# ZDR5V.net
KiCad netlist of a schematic drawn in EAGLE
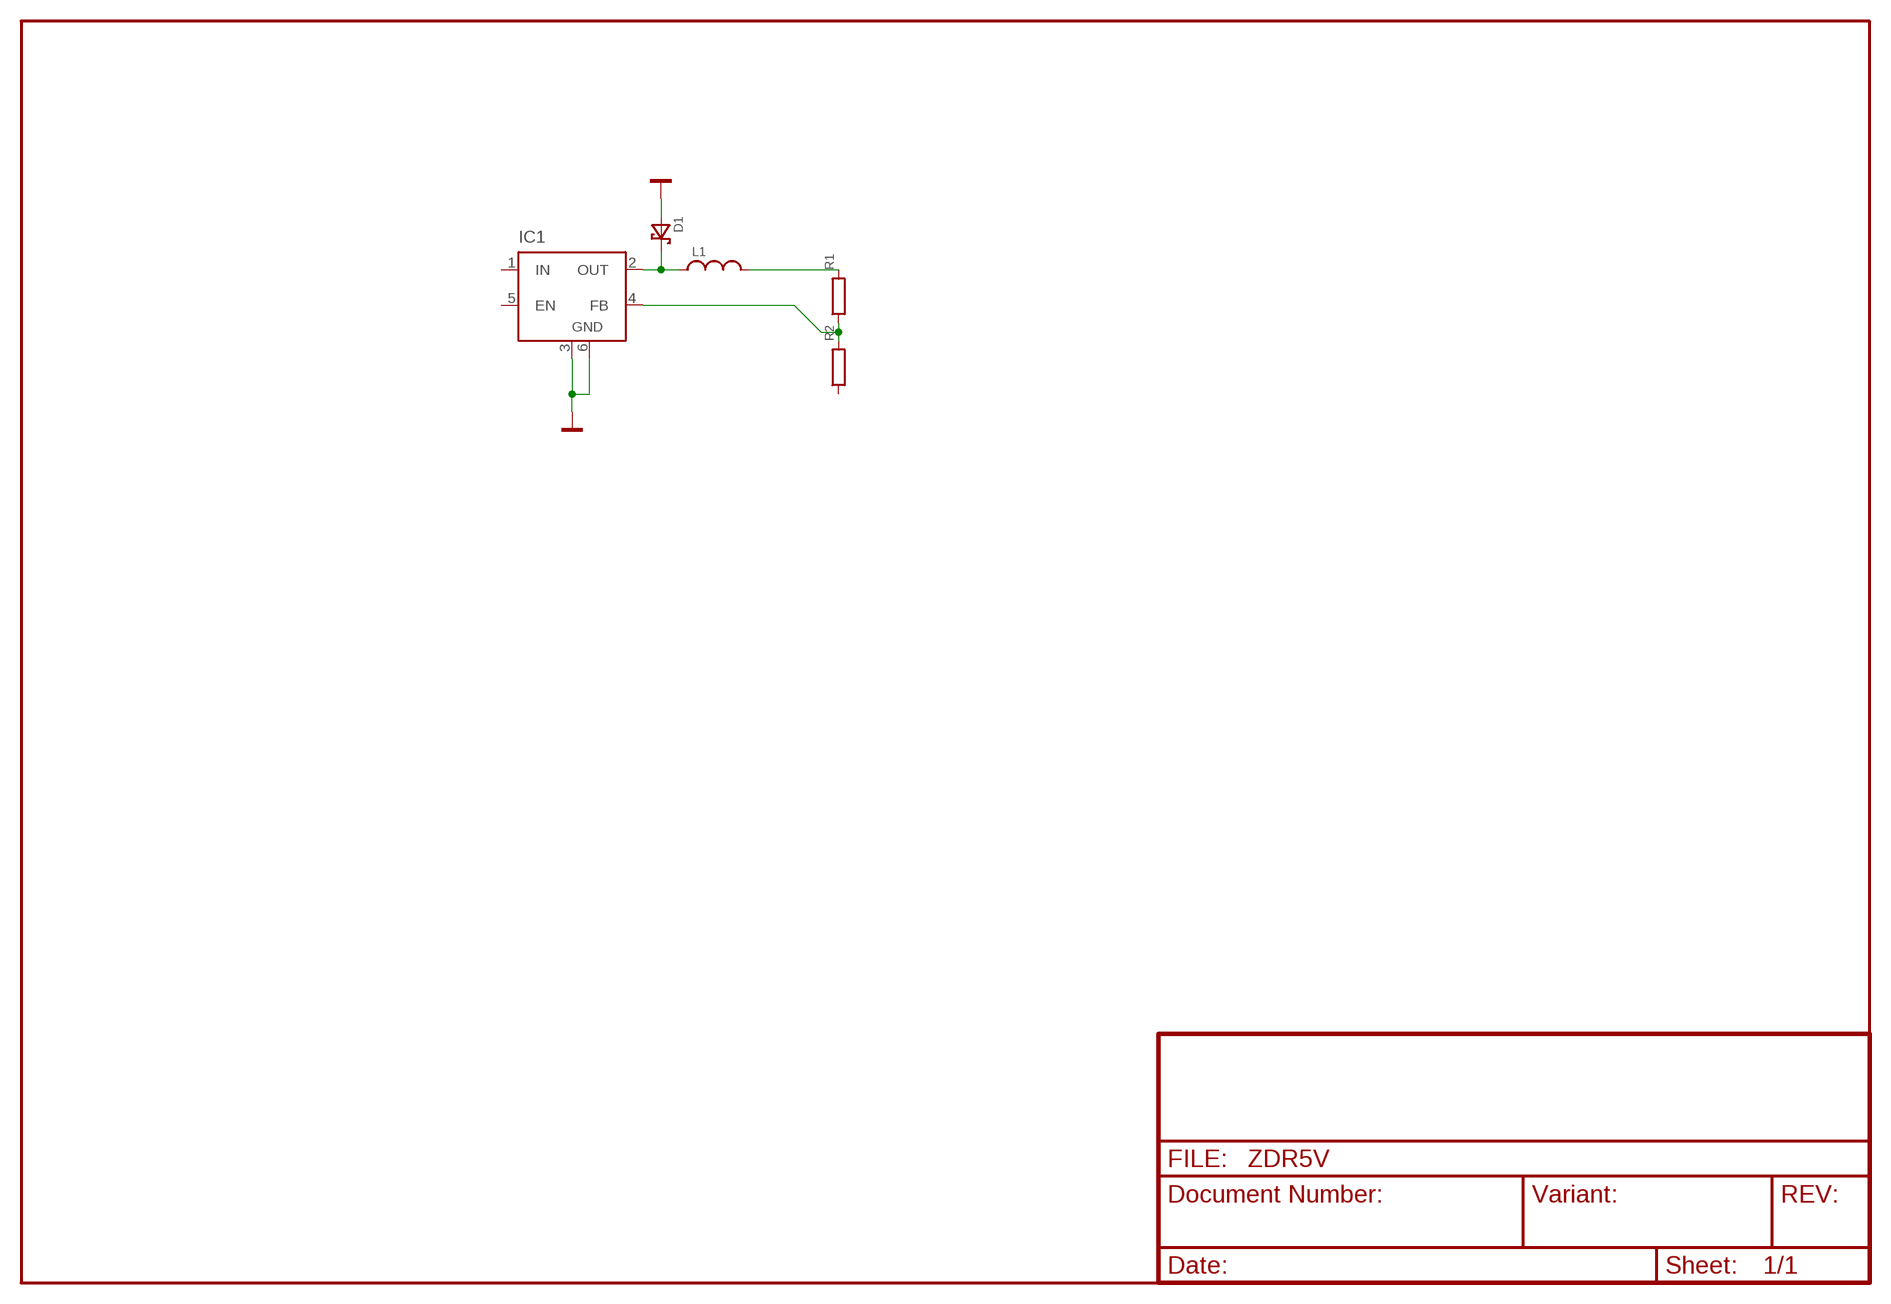
[diagram p0: schematic, sheet 1]

(export (version "E")
  (design (tool "Eeschema 10.0.6"))
  (components
    (comp (ref "D1")
      (value "D_SCHOTKY_SMB")
      (footprint "eagle-import:D_SMB")
      (libsource (lib "eagle-import") (part "D_SCHOTKY_SMB"))
    )
    (comp (ref "IC1")
      (value "LM2596S")
      (footprint "eagle-import:TO263-5")
      (libsource (lib "eagle-import") (part "LM2596S"))
    )
    (comp (ref "L1")
      (value "L_DE1209")
      (footprint "eagle-import:DE1209")
      (libsource (lib "eagle-import") (part "L_DE1209"))
    )
    (comp (ref "R1")
      (value "R_R0805")
      (footprint "eagle-import:0805")
      (libsource (lib "eagle-import") (part "R_R0805"))
    )
    (comp (ref "R2")
      (value "R_R0805")
      (footprint "eagle-import:0805")
      (libsource (lib "eagle-import") (part "R_R0805"))
    )
  )
  (nets
    (net (code "1") (name "GND") (class "Default")
      (node (ref "D1") (pin "A") (pinfunction "A_A") (pintype "passive"))
      (node (ref "IC1") (pin "3") (pinfunction "GND_3") (pintype "power_in"))
      (node (ref "IC1") (pin "6") (pinfunction "GND_6") (pintype "power_in"))
    )
    (net (code "2") (name "Net-(IC1-FB)") (class "Default")
      (node (ref "IC1") (pin "4") (pinfunction "FB_4") (pintype "input"))
      (node (ref "R1") (pin "1") (pinfunction "1_1") (pintype "passive"))
      (node (ref "R2") (pin "2") (pinfunction "2_2") (pintype "passive"))
    )
    (net (code "3") (name "Net-(IC1-OUT)") (class "Default")
      (node (ref "D1") (pin "K") (pinfunction "K_K") (pintype "passive"))
      (node (ref "IC1") (pin "2") (pinfunction "OUT_2") (pintype "output"))
      (node (ref "L1") (pin "2") (pinfunction "2_2") (pintype "passive"))
    )
    (net (code "4") (name "Net-(L1-Pad1)") (class "Default")
      (node (ref "L1") (pin "1") (pinfunction "1_1") (pintype "passive"))
      (node (ref "R1") (pin "2") (pinfunction "2_2") (pintype "passive"))
    )
    (net (code "5") (name "unconnected-(IC1-EN-Pad5)") (class "Default")
      (node (ref "IC1") (pin "5") (pinfunction "EN_5") (pintype "input"))
    )
    (net (code "6") (name "unconnected-(IC1-IN-Pad1)") (class "Default")
      (node (ref "IC1") (pin "1") (pinfunction "IN_1") (pintype "input"))
    )
    (net (code "7") (name "unconnected-(R2-Pad1)") (class "Default")
      (node (ref "R2") (pin "1") (pinfunction "1_1") (pintype "passive"))
    )
  )
)
